# Interconnect_board_limit_switches_v1p3.net
KiCad netlist of a schematic drawn in EAGLE
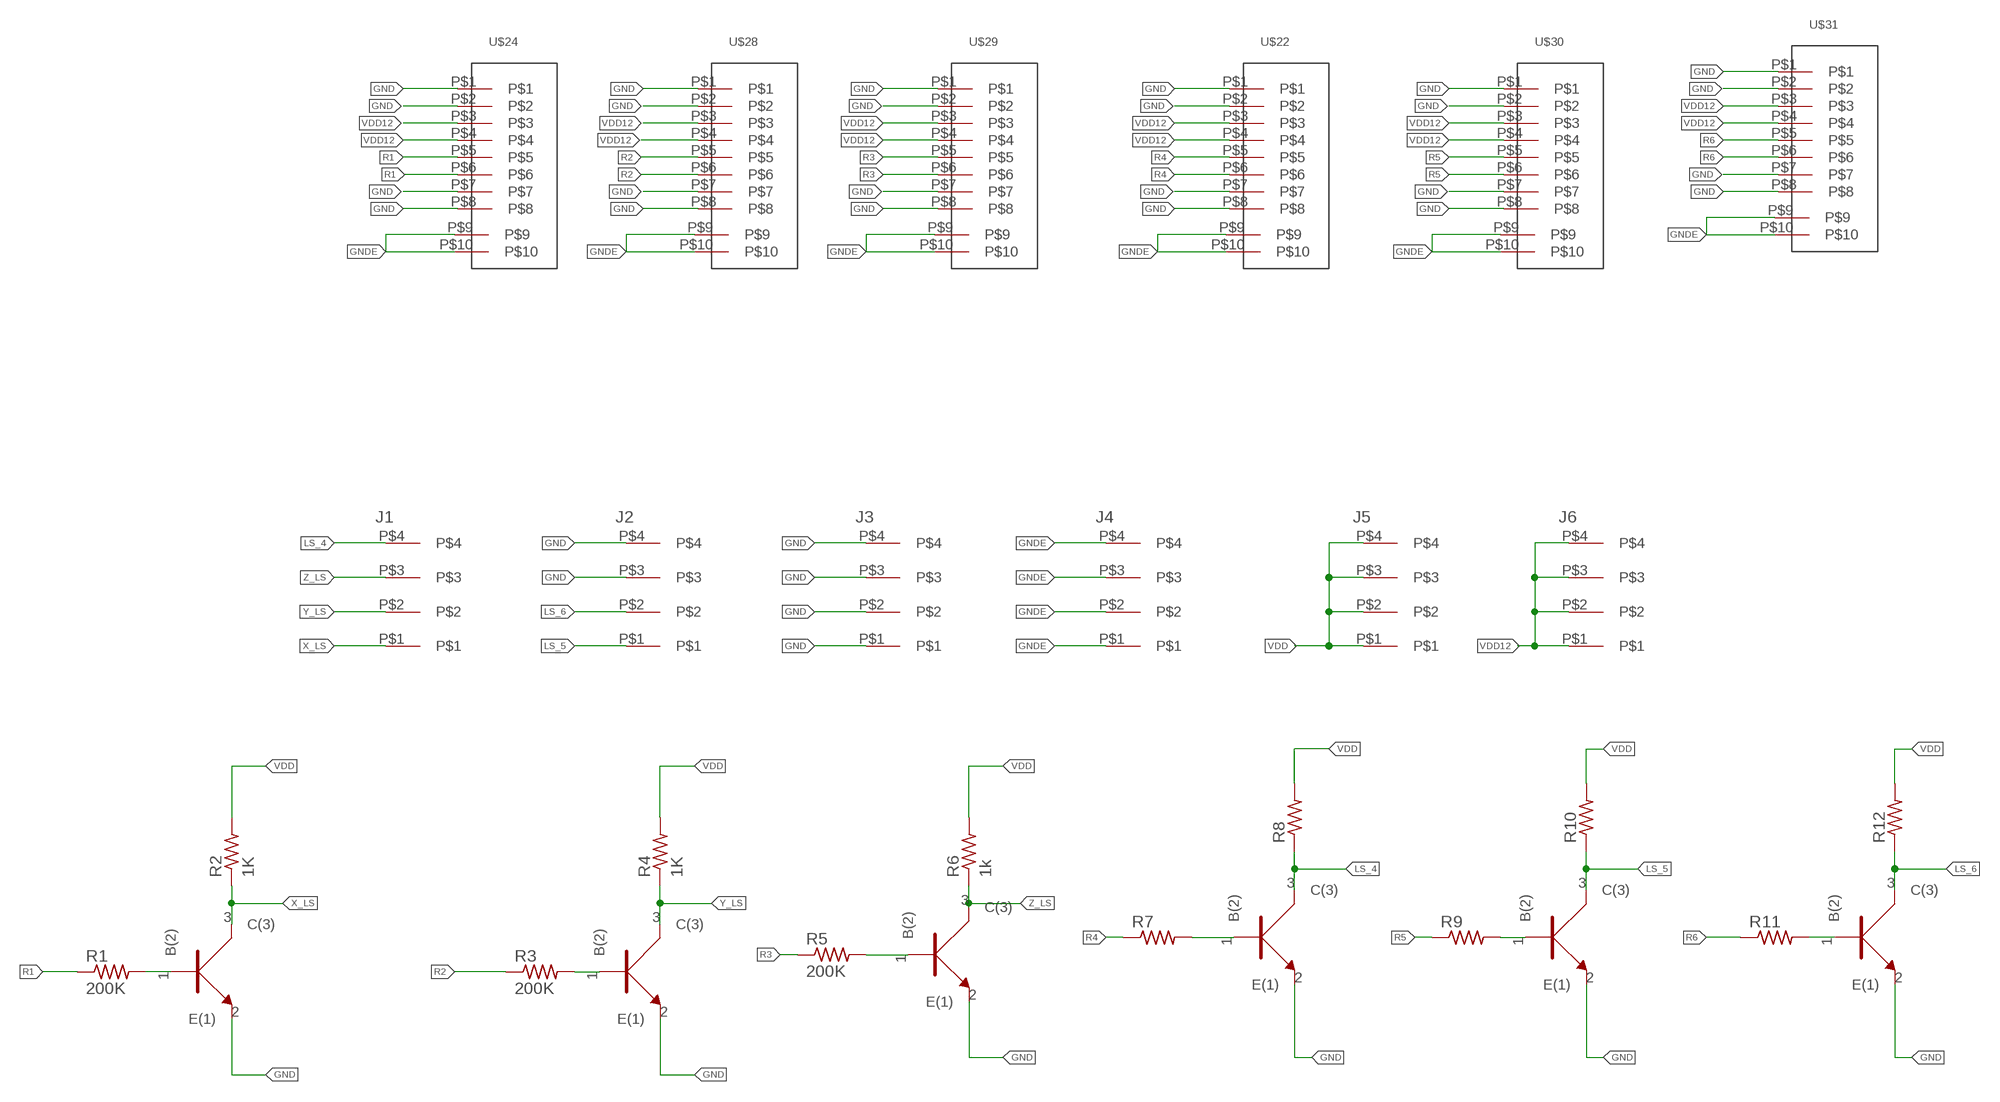
[diagram p0: schematic, sheet 1]

(export (version "E")
  (design (tool "Eeschema 10.0.6"))
  (components
    (comp (ref "J1")
      (value "3.81MM_1_X_4_RT_ANGLE_PLUG_HEADER")
      (footprint "eagle-import:1X4_3.81MM_PITCH")
      (libsource (lib "eagle-import") (part "3.81MM_1_X_4_RT_ANGLE_PLUG_HEADER"))
    )
    (comp (ref "J2")
      (value "3.81MM_1_X_4_RT_ANGLE_PLUG_HEADER")
      (footprint "eagle-import:1X4_3.81MM_PITCH")
      (libsource (lib "eagle-import") (part "3.81MM_1_X_4_RT_ANGLE_PLUG_HEADER"))
    )
    (comp (ref "J3")
      (value "3.81MM_1_X_4_RT_ANGLE_PLUG_HEADER")
      (footprint "eagle-import:1X4_3.81MM_PITCH")
      (libsource (lib "eagle-import") (part "3.81MM_1_X_4_RT_ANGLE_PLUG_HEADER"))
    )
    (comp (ref "J4")
      (value "3.81MM_1_X_4_RT_ANGLE_PLUG_HEADER")
      (footprint "eagle-import:1X4_3.81MM_PITCH")
      (libsource (lib "eagle-import") (part "3.81MM_1_X_4_RT_ANGLE_PLUG_HEADER"))
    )
    (comp (ref "J5")
      (value "3.81MM_1_X_4_RT_ANGLE_PLUG_HEADER")
      (footprint "eagle-import:1X4_3.81MM_PITCH")
      (libsource (lib "eagle-import") (part "3.81MM_1_X_4_RT_ANGLE_PLUG_HEADER"))
    )
    (comp (ref "J6")
      (value "3.81MM_1_X_4_RT_ANGLE_PLUG_HEADER")
      (footprint "eagle-import:1X4_3.81MM_PITCH")
      (libsource (lib "eagle-import") (part "3.81MM_1_X_4_RT_ANGLE_PLUG_HEADER"))
    )
    (comp (ref "R1")
      (value "200K")
      (footprint "eagle-import:0805")
      (libsource (lib "eagle-import") (part "R_0805"))
    )
    (comp (ref "R2")
      (value "1K")
      (footprint "eagle-import:0805")
      (libsource (lib "eagle-import") (part "R_0805"))
    )
    (comp (ref "R3")
      (value "200K")
      (footprint "eagle-import:0805")
      (libsource (lib "eagle-import") (part "R_0805"))
    )
    (comp (ref "R4")
      (value "1K")
      (footprint "eagle-import:0805")
      (libsource (lib "eagle-import") (part "R_0805"))
    )
    (comp (ref "R5")
      (value "200K")
      (footprint "eagle-import:0805")
      (libsource (lib "eagle-import") (part "R_0805"))
    )
    (comp (ref "R6")
      (value "1k")
      (footprint "eagle-import:0805")
      (libsource (lib "eagle-import") (part "R_0805"))
    )
    (comp (ref "R7")
      (value "R_0805")
      (footprint "eagle-import:0805")
      (libsource (lib "eagle-import") (part "R_0805"))
    )
    (comp (ref "R8")
      (value "R_0805")
      (footprint "eagle-import:0805")
      (libsource (lib "eagle-import") (part "R_0805"))
    )
    (comp (ref "R9")
      (value "R_0805")
      (footprint "eagle-import:0805")
      (libsource (lib "eagle-import") (part "R_0805"))
    )
    (comp (ref "R10")
      (value "R_0805")
      (footprint "eagle-import:0805")
      (libsource (lib "eagle-import") (part "R_0805"))
    )
    (comp (ref "R11")
      (value "R_0805")
      (footprint "eagle-import:0805")
      (libsource (lib "eagle-import") (part "R_0805"))
    )
    (comp (ref "R12")
      (value "R_0805")
      (footprint "eagle-import:0805")
      (libsource (lib "eagle-import") (part "R_0805"))
    )
    (comp (ref "U$22")
      (value "RJ45_SMTRJ")
      (footprint "eagle-import:RJ45_SMT")
      (libsource (lib "eagle-import") (part "RJ45_SMTRJ"))
    )
    (comp (ref "U$24")
      (value "RJ45_SMTRJ")
      (footprint "eagle-import:RJ45_SMT")
      (libsource (lib "eagle-import") (part "RJ45_SMTRJ"))
    )
    (comp (ref "U$28")
      (value "RJ45_SMTRJ")
      (footprint "eagle-import:RJ45_SMT")
      (libsource (lib "eagle-import") (part "RJ45_SMTRJ"))
    )
    (comp (ref "U$29")
      (value "RJ45_SMTRJ")
      (footprint "eagle-import:RJ45_SMT")
      (libsource (lib "eagle-import") (part "RJ45_SMTRJ"))
    )
    (comp (ref "U$30")
      (value "RJ45_SMTRJ")
      (footprint "eagle-import:RJ45_SMT")
      (libsource (lib "eagle-import") (part "RJ45_SMTRJ"))
    )
    (comp (ref "U$31")
      (value "RJ45_SMTRJ")
      (footprint "eagle-import:RJ45_SMT")
      (libsource (lib "eagle-import") (part "RJ45_SMTRJ"))
    )
    (comp (ref "U1")
      (value "BC846BW")
      (footprint "eagle-import:SOT323")
      (libsource (lib "eagle-import") (part "BC846BW"))
    )
    (comp (ref "U2")
      (value "BC846BW")
      (footprint "eagle-import:SOT323")
      (libsource (lib "eagle-import") (part "BC846BW"))
    )
    (comp (ref "U3")
      (value "BC846BW")
      (footprint "eagle-import:SOT323")
      (libsource (lib "eagle-import") (part "BC846BW"))
    )
    (comp (ref "U4")
      (value "BC846BW")
      (footprint "eagle-import:SOT323")
      (libsource (lib "eagle-import") (part "BC846BW"))
    )
    (comp (ref "U5")
      (value "BC846BW")
      (footprint "eagle-import:SOT323")
      (libsource (lib "eagle-import") (part "BC846BW"))
    )
    (comp (ref "U6")
      (value "BC846BW")
      (footprint "eagle-import:SOT323")
      (libsource (lib "eagle-import") (part "BC846BW"))
    )
  )
  (nets
    (net (code "1") (name "GND") (class "Default")
      (node (ref "J2") (pin "P$3") (pinfunction "P$3_P$3") (pintype "bidirectional"))
      (node (ref "J2") (pin "P$4") (pinfunction "P$4_P$4") (pintype "bidirectional"))
      (node (ref "J3") (pin "P$1") (pinfunction "P$1_P$1") (pintype "bidirectional"))
      (node (ref "J3") (pin "P$2") (pinfunction "P$2_P$2") (pintype "bidirectional"))
      (node (ref "J3") (pin "P$3") (pinfunction "P$3_P$3") (pintype "bidirectional"))
      (node (ref "J3") (pin "P$4") (pinfunction "P$4_P$4") (pintype "bidirectional"))
      (node (ref "U$22") (pin "P$1") (pinfunction "P$1_P$1") (pintype "bidirectional"))
      (node (ref "U$22") (pin "P$2") (pinfunction "P$2_P$2") (pintype "bidirectional"))
      (node (ref "U$22") (pin "P$7") (pinfunction "P$7_P$7") (pintype "bidirectional"))
      (node (ref "U$22") (pin "P$8") (pinfunction "P$8_P$8") (pintype "bidirectional"))
      (node (ref "U$24") (pin "P$1") (pinfunction "P$1_P$1") (pintype "bidirectional"))
      (node (ref "U$24") (pin "P$2") (pinfunction "P$2_P$2") (pintype "bidirectional"))
      (node (ref "U$24") (pin "P$7") (pinfunction "P$7_P$7") (pintype "bidirectional"))
      (node (ref "U$24") (pin "P$8") (pinfunction "P$8_P$8") (pintype "bidirectional"))
      (node (ref "U$28") (pin "P$1") (pinfunction "P$1_P$1") (pintype "bidirectional"))
      (node (ref "U$28") (pin "P$2") (pinfunction "P$2_P$2") (pintype "bidirectional"))
      (node (ref "U$28") (pin "P$7") (pinfunction "P$7_P$7") (pintype "bidirectional"))
      (node (ref "U$28") (pin "P$8") (pinfunction "P$8_P$8") (pintype "bidirectional"))
      (node (ref "U$29") (pin "P$1") (pinfunction "P$1_P$1") (pintype "bidirectional"))
      (node (ref "U$29") (pin "P$2") (pinfunction "P$2_P$2") (pintype "bidirectional"))
      (node (ref "U$29") (pin "P$7") (pinfunction "P$7_P$7") (pintype "bidirectional"))
      (node (ref "U$29") (pin "P$8") (pinfunction "P$8_P$8") (pintype "bidirectional"))
      (node (ref "U$30") (pin "P$1") (pinfunction "P$1_P$1") (pintype "bidirectional"))
      (node (ref "U$30") (pin "P$2") (pinfunction "P$2_P$2") (pintype "bidirectional"))
      (node (ref "U$30") (pin "P$7") (pinfunction "P$7_P$7") (pintype "bidirectional"))
      (node (ref "U$30") (pin "P$8") (pinfunction "P$8_P$8") (pintype "bidirectional"))
      (node (ref "U$31") (pin "P$1") (pinfunction "P$1_P$1") (pintype "bidirectional"))
      (node (ref "U$31") (pin "P$2") (pinfunction "P$2_P$2") (pintype "bidirectional"))
      (node (ref "U$31") (pin "P$7") (pinfunction "P$7_P$7") (pintype "bidirectional"))
      (node (ref "U$31") (pin "P$8") (pinfunction "P$8_P$8") (pintype "bidirectional"))
      (node (ref "U1") (pin "2") (pinfunction "E(1)_2") (pintype "output"))
      (node (ref "U2") (pin "2") (pinfunction "E(1)_2") (pintype "output"))
      (node (ref "U3") (pin "2") (pinfunction "E(1)_2") (pintype "output"))
      (node (ref "U4") (pin "2") (pinfunction "E(1)_2") (pintype "output"))
      (node (ref "U5") (pin "2") (pinfunction "E(1)_2") (pintype "output"))
      (node (ref "U6") (pin "2") (pinfunction "E(1)_2") (pintype "output"))
    )
    (net (code "2") (name "GNDE") (class "Default")
      (node (ref "J4") (pin "P$1") (pinfunction "P$1_P$1") (pintype "bidirectional"))
      (node (ref "J4") (pin "P$2") (pinfunction "P$2_P$2") (pintype "bidirectional"))
      (node (ref "J4") (pin "P$3") (pinfunction "P$3_P$3") (pintype "bidirectional"))
      (node (ref "J4") (pin "P$4") (pinfunction "P$4_P$4") (pintype "bidirectional"))
      (node (ref "U$22") (pin "P$10") (pinfunction "P$10_P$10") (pintype "bidirectional"))
      (node (ref "U$22") (pin "P$9") (pinfunction "P$9_P$9") (pintype "bidirectional"))
      (node (ref "U$24") (pin "P$10") (pinfunction "P$10_P$10") (pintype "bidirectional"))
      (node (ref "U$24") (pin "P$9") (pinfunction "P$9_P$9") (pintype "bidirectional"))
      (node (ref "U$28") (pin "P$10") (pinfunction "P$10_P$10") (pintype "bidirectional"))
      (node (ref "U$28") (pin "P$9") (pinfunction "P$9_P$9") (pintype "bidirectional"))
      (node (ref "U$29") (pin "P$10") (pinfunction "P$10_P$10") (pintype "bidirectional"))
      (node (ref "U$29") (pin "P$9") (pinfunction "P$9_P$9") (pintype "bidirectional"))
      (node (ref "U$30") (pin "P$10") (pinfunction "P$10_P$10") (pintype "bidirectional"))
      (node (ref "U$30") (pin "P$9") (pinfunction "P$9_P$9") (pintype "bidirectional"))
      (node (ref "U$31") (pin "P$10") (pinfunction "P$10_P$10") (pintype "bidirectional"))
      (node (ref "U$31") (pin "P$9") (pinfunction "P$9_P$9") (pintype "bidirectional"))
    )
    (net (code "3") (name "LS_4") (class "Default")
      (node (ref "J1") (pin "P$4") (pinfunction "P$4_P$4") (pintype "bidirectional"))
      (node (ref "R8") (pin "1") (pinfunction "1_1") (pintype "passive"))
      (node (ref "U4") (pin "3") (pinfunction "C(3)_3") (pintype "input"))
    )
    (net (code "4") (name "LS_5") (class "Default")
      (node (ref "J2") (pin "P$1") (pinfunction "P$1_P$1") (pintype "bidirectional"))
      (node (ref "R10") (pin "1") (pinfunction "1_1") (pintype "passive"))
      (node (ref "U5") (pin "3") (pinfunction "C(3)_3") (pintype "input"))
    )
    (net (code "5") (name "LS_6") (class "Default")
      (node (ref "J2") (pin "P$2") (pinfunction "P$2_P$2") (pintype "bidirectional"))
      (node (ref "R12") (pin "1") (pinfunction "1_1") (pintype "passive"))
      (node (ref "U6") (pin "3") (pinfunction "C(3)_3") (pintype "input"))
    )
    (net (code "6") (name "Net-(U1-B(2))") (class "Default")
      (node (ref "R1") (pin "2") (pinfunction "2_2") (pintype "passive"))
      (node (ref "U1") (pin "1") (pinfunction "B(2)_1") (pintype "input"))
    )
    (net (code "7") (name "Net-(U2-B(2))") (class "Default")
      (node (ref "R3") (pin "2") (pinfunction "2_2") (pintype "passive"))
      (node (ref "U2") (pin "1") (pinfunction "B(2)_1") (pintype "input"))
    )
    (net (code "8") (name "Net-(U3-B(2))") (class "Default")
      (node (ref "R5") (pin "2") (pinfunction "2_2") (pintype "passive"))
      (node (ref "U3") (pin "1") (pinfunction "B(2)_1") (pintype "input"))
    )
    (net (code "9") (name "Net-(U4-B(2))") (class "Default")
      (node (ref "R7") (pin "2") (pinfunction "2_2") (pintype "passive"))
      (node (ref "U4") (pin "1") (pinfunction "B(2)_1") (pintype "input"))
    )
    (net (code "10") (name "Net-(U5-B(2))") (class "Default")
      (node (ref "R9") (pin "2") (pinfunction "2_2") (pintype "passive"))
      (node (ref "U5") (pin "1") (pinfunction "B(2)_1") (pintype "input"))
    )
    (net (code "11") (name "Net-(U6-B(2))") (class "Default")
      (node (ref "R11") (pin "2") (pinfunction "2_2") (pintype "passive"))
      (node (ref "U6") (pin "1") (pinfunction "B(2)_1") (pintype "input"))
    )
    (net (code "12") (name "R1") (class "Default")
      (node (ref "R1") (pin "1") (pinfunction "1_1") (pintype "passive"))
      (node (ref "U$24") (pin "P$5") (pinfunction "P$5_P$5") (pintype "bidirectional"))
      (node (ref "U$24") (pin "P$6") (pinfunction "P$6_P$6") (pintype "bidirectional"))
    )
    (net (code "13") (name "R2") (class "Default")
      (node (ref "R3") (pin "1") (pinfunction "1_1") (pintype "passive"))
      (node (ref "U$28") (pin "P$5") (pinfunction "P$5_P$5") (pintype "bidirectional"))
      (node (ref "U$28") (pin "P$6") (pinfunction "P$6_P$6") (pintype "bidirectional"))
    )
    (net (code "14") (name "R3") (class "Default")
      (node (ref "R5") (pin "1") (pinfunction "1_1") (pintype "passive"))
      (node (ref "U$29") (pin "P$5") (pinfunction "P$5_P$5") (pintype "bidirectional"))
      (node (ref "U$29") (pin "P$6") (pinfunction "P$6_P$6") (pintype "bidirectional"))
    )
    (net (code "15") (name "R4") (class "Default")
      (node (ref "R7") (pin "1") (pinfunction "1_1") (pintype "passive"))
      (node (ref "U$22") (pin "P$5") (pinfunction "P$5_P$5") (pintype "bidirectional"))
      (node (ref "U$22") (pin "P$6") (pinfunction "P$6_P$6") (pintype "bidirectional"))
    )
    (net (code "16") (name "R5") (class "Default")
      (node (ref "R9") (pin "1") (pinfunction "1_1") (pintype "passive"))
      (node (ref "U$30") (pin "P$5") (pinfunction "P$5_P$5") (pintype "bidirectional"))
      (node (ref "U$30") (pin "P$6") (pinfunction "P$6_P$6") (pintype "bidirectional"))
    )
    (net (code "17") (name "R6") (class "Default")
      (node (ref "R11") (pin "1") (pinfunction "1_1") (pintype "passive"))
      (node (ref "U$31") (pin "P$5") (pinfunction "P$5_P$5") (pintype "bidirectional"))
      (node (ref "U$31") (pin "P$6") (pinfunction "P$6_P$6") (pintype "bidirectional"))
    )
    (net (code "18") (name "VDD") (class "Default")
      (node (ref "J5") (pin "P$1") (pinfunction "P$1_P$1") (pintype "bidirectional"))
      (node (ref "J5") (pin "P$2") (pinfunction "P$2_P$2") (pintype "bidirectional"))
      (node (ref "J5") (pin "P$3") (pinfunction "P$3_P$3") (pintype "bidirectional"))
      (node (ref "J5") (pin "P$4") (pinfunction "P$4_P$4") (pintype "bidirectional"))
      (node (ref "R10") (pin "2") (pinfunction "2_2") (pintype "passive"))
      (node (ref "R12") (pin "2") (pinfunction "2_2") (pintype "passive"))
      (node (ref "R2") (pin "2") (pinfunction "2_2") (pintype "passive"))
      (node (ref "R4") (pin "2") (pinfunction "2_2") (pintype "passive"))
      (node (ref "R6") (pin "2") (pinfunction "2_2") (pintype "passive"))
      (node (ref "R8") (pin "2") (pinfunction "2_2") (pintype "passive"))
    )
    (net (code "19") (name "VDD12") (class "Default")
      (node (ref "J6") (pin "P$1") (pinfunction "P$1_P$1") (pintype "bidirectional"))
      (node (ref "J6") (pin "P$2") (pinfunction "P$2_P$2") (pintype "bidirectional"))
      (node (ref "J6") (pin "P$3") (pinfunction "P$3_P$3") (pintype "bidirectional"))
      (node (ref "J6") (pin "P$4") (pinfunction "P$4_P$4") (pintype "bidirectional"))
      (node (ref "U$22") (pin "P$3") (pinfunction "P$3_P$3") (pintype "bidirectional"))
      (node (ref "U$22") (pin "P$4") (pinfunction "P$4_P$4") (pintype "bidirectional"))
      (node (ref "U$24") (pin "P$3") (pinfunction "P$3_P$3") (pintype "bidirectional"))
      (node (ref "U$24") (pin "P$4") (pinfunction "P$4_P$4") (pintype "bidirectional"))
      (node (ref "U$28") (pin "P$3") (pinfunction "P$3_P$3") (pintype "bidirectional"))
      (node (ref "U$28") (pin "P$4") (pinfunction "P$4_P$4") (pintype "bidirectional"))
      (node (ref "U$29") (pin "P$3") (pinfunction "P$3_P$3") (pintype "bidirectional"))
      (node (ref "U$29") (pin "P$4") (pinfunction "P$4_P$4") (pintype "bidirectional"))
      (node (ref "U$30") (pin "P$3") (pinfunction "P$3_P$3") (pintype "bidirectional"))
      (node (ref "U$30") (pin "P$4") (pinfunction "P$4_P$4") (pintype "bidirectional"))
      (node (ref "U$31") (pin "P$3") (pinfunction "P$3_P$3") (pintype "bidirectional"))
      (node (ref "U$31") (pin "P$4") (pinfunction "P$4_P$4") (pintype "bidirectional"))
    )
    (net (code "20") (name "X_LS") (class "Default")
      (node (ref "J1") (pin "P$1") (pinfunction "P$1_P$1") (pintype "bidirectional"))
      (node (ref "R2") (pin "1") (pinfunction "1_1") (pintype "passive"))
      (node (ref "U1") (pin "3") (pinfunction "C(3)_3") (pintype "input"))
    )
    (net (code "21") (name "Y_LS") (class "Default")
      (node (ref "J1") (pin "P$2") (pinfunction "P$2_P$2") (pintype "bidirectional"))
      (node (ref "R4") (pin "1") (pinfunction "1_1") (pintype "passive"))
      (node (ref "U2") (pin "3") (pinfunction "C(3)_3") (pintype "input"))
    )
    (net (code "22") (name "Z_LS") (class "Default")
      (node (ref "J1") (pin "P$3") (pinfunction "P$3_P$3") (pintype "bidirectional"))
      (node (ref "R6") (pin "1") (pinfunction "1_1") (pintype "passive"))
      (node (ref "U3") (pin "3") (pinfunction "C(3)_3") (pintype "input"))
    )
  )
)
